# LED_Driver.net
KiCad netlist of a schematic drawn in Altium Designer
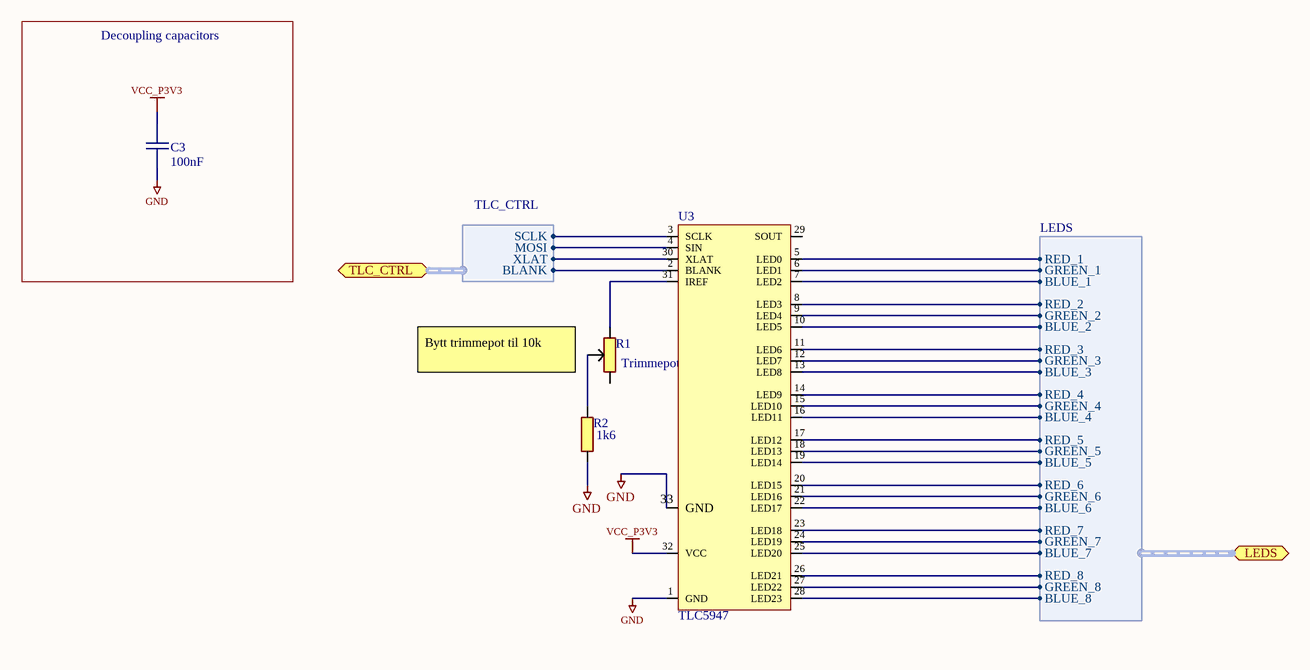
[diagram p0: LED Driver.SchDoc]

(export (version "E")
  (design (tool "Eeschema 10.0.6"))
  (components
    (comp (ref "C3")
      (value "100nF")
      (footprint "CAPC0603(1608)55_N")
      (description "X7R 50V 5%")
      (libsource (lib "OVLib") (part "CAP"))
    )
    (comp (ref "R1")
      (value "Trimmepot 500ohm")
      (footprint "TRIMPOT_3006P")
      (description "15 turn, horizontal")
      (libsource (lib "OVLib") (part "Potmeter"))
    )
    (comp (ref "R2")
      (value "1k6")
      (footprint "RESC0603(1608)_N")
      (description "0.1W 1% Thick film resistor")
      (libsource (lib "OVLib") (part "Resistor2"))
    )
    (comp (ref "U3") (value "TLC5947") (footprint "TLC5947") (libsource (lib "Schlib1") (part "TLC5947")))
  )
  (nets
    (net (code "3") (name "/BLANK") (class "Default")
      (node (ref "U3") (pin "2") (pinfunction "BLANK_2") (pintype "passive"))
    )
    (net (code "4") (name "/BLUE_1") (class "Default")
      (node (ref "U3") (pin "7") (pinfunction "LED2_7") (pintype "passive"))
    )
    (net (code "5") (name "/BLUE_2") (class "Default")
      (node (ref "U3") (pin "10") (pinfunction "LED5_10") (pintype "passive"))
    )
    (net (code "6") (name "/BLUE_3") (class "Default")
      (node (ref "U3") (pin "13") (pinfunction "LED8_13") (pintype "passive"))
    )
    (net (code "7") (name "/BLUE_4") (class "Default")
      (node (ref "U3") (pin "16") (pinfunction "LED11_16") (pintype "passive"))
    )
    (net (code "8") (name "/BLUE_5") (class "Default")
      (node (ref "U3") (pin "19") (pinfunction "LED14_19") (pintype "passive"))
    )
    (net (code "9") (name "/BLUE_6") (class "Default")
      (node (ref "U3") (pin "22") (pinfunction "LED17_22") (pintype "passive"))
    )
    (net (code "10") (name "/BLUE_7") (class "Default")
      (node (ref "U3") (pin "25") (pinfunction "LED20_25") (pintype "passive"))
    )
    (net (code "11") (name "/BLUE_8") (class "Default")
      (node (ref "U3") (pin "28") (pinfunction "LED23_28") (pintype "passive"))
    )
    (net (code "12") (name "/GREEN_1") (class "Default")
      (node (ref "U3") (pin "6") (pinfunction "LED1_6") (pintype "passive"))
    )
    (net (code "13") (name "/GREEN_2") (class "Default")
      (node (ref "U3") (pin "9") (pinfunction "LED4_9") (pintype "passive"))
    )
    (net (code "14") (name "/GREEN_3") (class "Default")
      (node (ref "U3") (pin "12") (pinfunction "LED7_12") (pintype "passive"))
    )
    (net (code "15") (name "/GREEN_4") (class "Default")
      (node (ref "U3") (pin "15") (pinfunction "LED10_15") (pintype "passive"))
    )
    (net (code "16") (name "/GREEN_5") (class "Default")
      (node (ref "U3") (pin "18") (pinfunction "LED13_18") (pintype "passive"))
    )
    (net (code "17") (name "/GREEN_6") (class "Default")
      (node (ref "U3") (pin "21") (pinfunction "LED16_21") (pintype "passive"))
    )
    (net (code "18") (name "/GREEN_7") (class "Default")
      (node (ref "U3") (pin "24") (pinfunction "LED19_24") (pintype "passive"))
    )
    (net (code "19") (name "/GREEN_8") (class "Default")
      (node (ref "U3") (pin "27") (pinfunction "LED22_27") (pintype "passive"))
    )
    (net (code "20") (name "/MOSI") (class "Default")
      (node (ref "U3") (pin "4") (pinfunction "SIN_4") (pintype "passive"))
    )
    (net (code "21") (name "/RED_1") (class "Default")
      (node (ref "U3") (pin "5") (pinfunction "LED0_5") (pintype "passive"))
    )
    (net (code "22") (name "/RED_2") (class "Default")
      (node (ref "U3") (pin "8") (pinfunction "LED3_8") (pintype "passive"))
    )
    (net (code "23") (name "/RED_3") (class "Default")
      (node (ref "U3") (pin "11") (pinfunction "LED6_11") (pintype "passive"))
    )
    (net (code "24") (name "/RED_4") (class "Default")
      (node (ref "U3") (pin "14") (pinfunction "LED9_14") (pintype "passive"))
    )
    (net (code "25") (name "/RED_5") (class "Default")
      (node (ref "U3") (pin "17") (pinfunction "LED12_17") (pintype "passive"))
    )
    (net (code "26") (name "/RED_6") (class "Default")
      (node (ref "U3") (pin "20") (pinfunction "LED15_20") (pintype "passive"))
    )
    (net (code "27") (name "/RED_7") (class "Default")
      (node (ref "U3") (pin "23") (pinfunction "LED18_23") (pintype "passive"))
    )
    (net (code "28") (name "/RED_8") (class "Default")
      (node (ref "U3") (pin "26") (pinfunction "LED21_26") (pintype "passive"))
    )
    (net (code "29") (name "/SCLK") (class "Default")
      (node (ref "U3") (pin "3") (pinfunction "SCLK_3") (pintype "passive"))
    )
    (net (code "30") (name "/XLAT") (class "Default")
      (node (ref "U3") (pin "30") (pinfunction "XLAT_30") (pintype "passive"))
    )
    (net (code "33") (name "GND") (class "Default")
      (node (ref "C3") (pin "1") (pinfunction "1_1") (pintype "passive"))
      (node (ref "R2") (pin "1") (pinfunction "1_1") (pintype "passive"))
      (node (ref "U3") (pin "1") (pinfunction "GND_1") (pintype "passive"))
      (node (ref "U3") (pin "33") (pinfunction "GND_33") (pintype "passive"))
    )
    (net (code "34") (name "Net-(R1-Pad2)") (class "Default")
      (node (ref "R1") (pin "2") (pinfunction "2_2") (pintype "passive"))
      (node (ref "R2") (pin "2") (pinfunction "2_2") (pintype "passive"))
    )
    (net (code "35") (name "Net-(U3-IREF)") (class "Default")
      (node (ref "R1") (pin "3") (pinfunction "3_3") (pintype "passive"))
      (node (ref "U3") (pin "31") (pinfunction "IREF_31") (pintype "passive"))
    )
    (net (code "36") (name "VCC_P3V3") (class "Default")
      (node (ref "C3") (pin "2") (pinfunction "2_2") (pintype "passive"))
      (node (ref "U3") (pin "32") (pinfunction "VCC_32") (pintype "passive"))
    )
    (net (code "37") (name "unconnected-(R1-Pad1)") (class "Default")
      (node (ref "R1") (pin "1") (pinfunction "1_1") (pintype "passive"))
    )
    (net (code "38") (name "unconnected-(U3-SOUT-Pad29)") (class "Default")
      (node (ref "U3") (pin "29") (pinfunction "SOUT_29") (pintype "passive"))
    )
  )
)
